# Debug_UART.net
KiCad netlist of a schematic drawn in Altium Designer
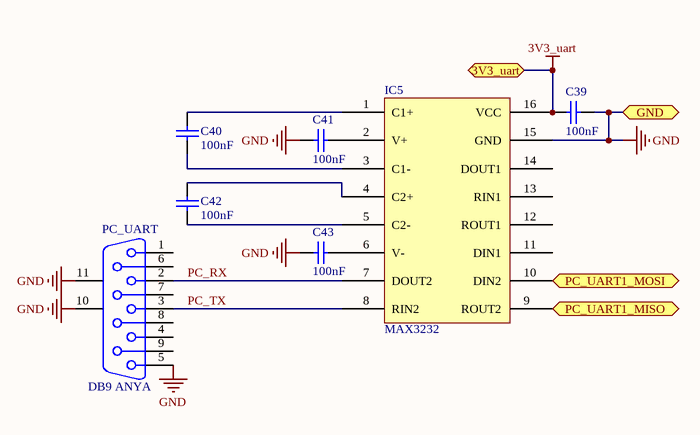
[diagram p0: Debug_UART.SchDoc]

(export (version "E")
  (design (tool "Eeschema 10.0.6"))
  (components
    (comp (ref "C39")
      (value "100nF")
      (footprint "FP_0603_CAP_080")
      (description "Capacitor")
      (fields (field (name "Comment") "Cap") (field (name "PUBLISHER") "Altium Limited"))
      (libsource (lib "Miscellaneous Devices") (part "Cap"))
    )
    (comp (ref "C40")
      (value "100nF")
      (footprint "FP_0603_CAP_080")
      (description "Capacitor")
      (fields (field (name "Comment") "Cap") (field (name "PUBLISHER") "Altium Limited"))
      (libsource (lib "Miscellaneous Devices") (part "Cap"))
    )
    (comp (ref "C41")
      (value "100nF")
      (footprint "FP_0603_CAP_080")
      (description "Capacitor")
      (fields (field (name "Comment") "Cap") (field (name "PUBLISHER") "Altium Limited"))
      (libsource (lib "Miscellaneous Devices") (part "Cap"))
    )
    (comp (ref "C42")
      (value "100nF")
      (footprint "FP_0603_CAP_080")
      (description "Capacitor")
      (fields (field (name "Comment") "Cap") (field (name "PUBLISHER") "Altium Limited"))
      (libsource (lib "Miscellaneous Devices") (part "Cap"))
    )
    (comp (ref "C43")
      (value "100nF")
      (footprint "FP_0603_CAP_080")
      (description "Capacitor")
      (fields (field (name "Comment") "Cap") (field (name "PUBLISHER") "Altium Limited"))
      (libsource (lib "Miscellaneous Devices") (part "Cap"))
    )
    (comp (ref "IC5") (value "MAX3232") (footprint "SOIC16") (libsource (lib "diploma") (part "MAX3232")))
    (comp (ref "PC_UART")
      (value "DB9 ANYA")
      (footprint "DB9_connector")
      (description "Receptacle Assembly, 9 Position, Right Angle")
      (fields (field (name "PUBLISHER") "Altium Limited"))
      (libsource (lib "Miscellaneous Connectors") (part "D Connector 9"))
    )
  )
  (nets
    (net (code "1") (name "/PC_RX") (class "Default")
      (node (ref "IC5") (pin "7") (pinfunction "DOUT2_7") (pintype "passive"))
      (node (ref "PC_UART") (pin "2") (pinfunction "2_2") (pintype "passive"))
    )
    (net (code "2") (name "/PC_TX") (class "Default")
      (node (ref "IC5") (pin "8") (pinfunction "RIN2_8") (pintype "passive"))
      (node (ref "PC_UART") (pin "3") (pinfunction "3_3") (pintype "passive"))
    )
    (net (code "3") (name "/PC_UART1_MISO") (class "Default")
      (node (ref "IC5") (pin "9") (pinfunction "ROUT2_9") (pintype "passive"))
    )
    (net (code "4") (name "/PC_UART1_MOSI") (class "Default")
      (node (ref "IC5") (pin "10") (pinfunction "DIN2_10") (pintype "passive"))
    )
    (net (code "5") (name "3V3_uart") (class "Default")
      (node (ref "C39") (pin "2") (pinfunction "2_2") (pintype "passive"))
      (node (ref "IC5") (pin "16") (pinfunction "VCC_16") (pintype "passive"))
    )
    (net (code "6") (name "GND") (class "Default")
      (node (ref "C39") (pin "1") (pinfunction "1_1") (pintype "passive"))
      (node (ref "C41") (pin "1") (pinfunction "1_1") (pintype "passive"))
      (node (ref "C43") (pin "1") (pinfunction "1_1") (pintype "passive"))
      (node (ref "IC5") (pin "15") (pinfunction "GND_15") (pintype "passive"))
      (node (ref "PC_UART") (pin "10") (pinfunction "MH1_10") (pintype "passive"))
      (node (ref "PC_UART") (pin "11") (pinfunction "MH2_11") (pintype "passive"))
      (node (ref "PC_UART") (pin "5") (pinfunction "5_5") (pintype "passive"))
    )
    (net (code "7") (name "Net-(IC5-C1+)") (class "Default")
      (node (ref "C40") (pin "2") (pinfunction "2_2") (pintype "passive"))
      (node (ref "IC5") (pin "1") (pinfunction "C1+_1") (pintype "passive"))
    )
    (net (code "8") (name "Net-(IC5-C1-)") (class "Default")
      (node (ref "C40") (pin "1") (pinfunction "1_1") (pintype "passive"))
      (node (ref "IC5") (pin "3") (pinfunction "C1-_3") (pintype "passive"))
    )
    (net (code "9") (name "Net-(IC5-C2+)") (class "Default")
      (node (ref "C42") (pin "2") (pinfunction "2_2") (pintype "passive"))
      (node (ref "IC5") (pin "4") (pinfunction "C2+_4") (pintype "passive"))
    )
    (net (code "10") (name "Net-(IC5-C2-)") (class "Default")
      (node (ref "C42") (pin "1") (pinfunction "1_1") (pintype "passive"))
      (node (ref "IC5") (pin "5") (pinfunction "C2-_5") (pintype "passive"))
    )
    (net (code "11") (name "Net-(IC5-V+)") (class "Default")
      (node (ref "C41") (pin "2") (pinfunction "2_2") (pintype "passive"))
      (node (ref "IC5") (pin "2") (pinfunction "V+_2") (pintype "passive"))
    )
    (net (code "12") (name "Net-(IC5-V-)") (class "Default")
      (node (ref "C43") (pin "2") (pinfunction "2_2") (pintype "passive"))
      (node (ref "IC5") (pin "6") (pinfunction "V-_6") (pintype "passive"))
    )
    (net (code "13") (name "unconnected-(IC5-DIN1-Pad11)") (class "Default")
      (node (ref "IC5") (pin "11") (pinfunction "DIN1_11") (pintype "passive"))
    )
    (net (code "14") (name "unconnected-(IC5-DOUT1-Pad14)") (class "Default")
      (node (ref "IC5") (pin "14") (pinfunction "DOUT1_14") (pintype "passive"))
    )
    (net (code "15") (name "unconnected-(IC5-RIN1-Pad13)") (class "Default")
      (node (ref "IC5") (pin "13") (pinfunction "RIN1_13") (pintype "passive"))
    )
    (net (code "16") (name "unconnected-(IC5-ROUT1-Pad12)") (class "Default")
      (node (ref "IC5") (pin "12") (pinfunction "ROUT1_12") (pintype "passive"))
    )
    (net (code "17") (name "unconnected-(PC_UART-Pad1)") (class "Default")
      (node (ref "PC_UART") (pin "1") (pinfunction "1_1") (pintype "passive"))
    )
    (net (code "18") (name "unconnected-(PC_UART-Pad4)") (class "Default")
      (node (ref "PC_UART") (pin "4") (pinfunction "4_4") (pintype "passive"))
    )
    (net (code "19") (name "unconnected-(PC_UART-Pad6)") (class "Default")
      (node (ref "PC_UART") (pin "6") (pinfunction "6_6") (pintype "passive"))
    )
    (net (code "20") (name "unconnected-(PC_UART-Pad7)") (class "Default")
      (node (ref "PC_UART") (pin "7") (pinfunction "7_7") (pintype "passive"))
    )
    (net (code "21") (name "unconnected-(PC_UART-Pad8)") (class "Default")
      (node (ref "PC_UART") (pin "8") (pinfunction "8_8") (pintype "passive"))
    )
    (net (code "22") (name "unconnected-(PC_UART-Pad9)") (class "Default")
      (node (ref "PC_UART") (pin "9") (pinfunction "9_9") (pintype "passive"))
    )
  )
)
